# power.net
KiCad netlist of a schematic drawn in Altium Designer
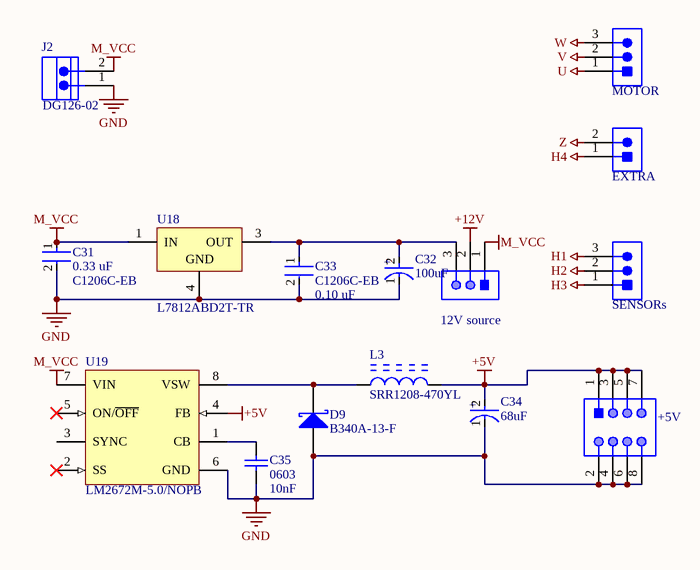
[diagram p0: power.SchDoc]

(export (version "E")
  (design (tool "Eeschema 10.0.6"))
  (components
    (comp (ref "+5V")
      (value "61300821121")
      (footprint "61300821121")
      (description "THT Vertical Pin Header WR-PHD, Pitch 2.54 mm, Dual Row, 8 pins")
      (fields (field (name "MANUFACTURER") "Wurth Elektronik") (field (name "PUBLISHER") "WurthElektronik"))
      (libsource (lib "Altium Content Vault") (part "WE-CN-2P-M-R8"))
    )
    (comp (ref "12V source")
      (value "61300311121")
      (footprint "61300311121")
      (description "THT Vertical Pin Header WR-PHD, Pitch 2.54 mm, Single Row, 3 pins")
      (fields (field (name "MANUFACTURER") "Wurth Elektronik") (field (name "PUBLISHER") "WurthElektronik"))
      (libsource (lib "Altium Content Vault") (part "WE-CN-1P-M-R3"))
    )
    (comp (ref "C31")
      (value "C1206C334M3VACTU")
      (footprint "FP-C1206C-EB-IPC_A")
      (description "CAP CER 0.33UF 25V Y5V 1206")
      (fields
        (field (name "CAPACITANCE") "0.33 uF")
        (field (name "PACKAGE") "C1206C-EB")
        (field (name "OCTOPART") "https://octopart.com/c1206c334m3vactu-kemet-9139506")
        (field (name "TOLERANCE") "0.2")
      )
      (libsource (lib "Altium Content Vault") (part "b4654b650e69147ec39a6b967a45e02"))
    )
    (comp (ref "C32")
      (value "PCR1J101MCL1GS")
      (footprint "FP-PCR1J101MCL1GS-MFG")
      (description "CAP ALUM POLY 100UF 20% 63V SMD")
      (fields
        (field (name "CAPACITANCE") "100uF")
        (field (name "MANUFACTURER") "Nichicon")
        (field (name "TOLERANCE") "20%")
      )
      (libsource (lib "Altium Content Vault") (part "cf48714ba7e38822c1575c7ec0b6d1f"))
    )
    (comp (ref "C33")
      (value "C1206C104KARACTU")
      (footprint "FP-C1206C-EB-IPC_A")
      (description "CAP CER 0.1UF 250V X7R 1206")
      (fields
        (field (name "PACKAGE") "C1206C-EB")
        (field (name "MANUFACTURER") "KEMET")
        (field (name "TOLERANCE") "0.1")
        (field (name "CAPACITANCE") "0.10 uF")
      )
      (libsource (lib "Altium Content Vault") (part "b4654b650e69147ec39a6b967a45e02"))
    )
    (comp (ref "C34")
      (value "PCR1J101MCL1GS")
      (footprint "FP-PCR1J101MCL1GS-MFG")
      (description "CAP ALUM POLY 100UF 20% 63V SMD")
      (fields
        (field (name "CAPACITANCE") "68uF")
        (field (name "MANUFACTURER") "Nichicon")
        (field (name "TOLERANCE") "20%")
      )
      (libsource (lib "Altium Content Vault") (part "cf48714ba7e38822c1575c7ec0b6d1f"))
    )
    (comp (ref "C35")
      (value "10nF")
      (footprint "CAPC0603(1608)100_M")
      (description "CAP 1nF 16V ±2% 0603 (1608 Metric) Thickness 1mm SMD")
      (fields
        (field (name "CASE-EIA") "0603")
        (field (name "TOLERANCE") "Â±2%")
        (field (name "Comment") "CAP 1nF 16V 0603(1608)")
      )
      (libsource (lib "Altium Content Vault") (part "CAP"))
    )
    (comp (ref "D9")
      (value "B340A-13-F")
      (footprint "DIOD-SMA-2_V")
      (libsource (lib "Altium Content Vault") (part "DSKY-AK-2"))
    )
    (comp (ref "EXTRA")
      (value "SCREW-5.0/5.08 2WAYS")
      (footprint "SCREW-5.0-2WAYS_V")
      (description "Socket, Screw Terminal Block, 2 Way, 5.0 mm Pitch, 90 Degree Angle, Through-Hole")
      (fields (field (name "MANUFACTURER") "No Vendor"))
      (libsource (lib "Altium Content Vault") (part "SCREW-2WAYS"))
    )
    (comp (ref "J2")
      (value "DG126-02")
      (footprint "CXKF-KF129C-2_V")
      (fields
        (field (name "PARTNUMBER") "KF129C-02P-14")
        (field (name "MANUFACTURER") "Cixi KaiFeng")
        (field (name "CONTACT") "Brass")
      )
      (libsource (lib "Altium Content Vault") (part "CXKF-KF129C-2"))
    )
    (comp (ref "L3")
      (value "SRR1208-470YL")
      (footprint "BOUR-SRR1280-2_V")
      (fields (field (name "TOLERANCE") "±20%") (field (name "MANUFACTURER") "Bourns"))
      (libsource (lib "Altium Content Vault") (part "IND-FERR-2"))
    )
    (comp (ref "MOTOR")
      (value "SCREW-5.0/5.08 3WAYS")
      (footprint "SCREW-5.0-3WAYS_V")
      (description "Socket, Screw Terminal Block, 3 Way, 5.0 mm Pitch, 90 Degree Angle, Through-Hole")
      (fields (field (name "MANUFACTURER") "No Vendor"))
      (libsource (lib "Altium Content Vault") (part "SCREW-3WAYS"))
    )
    (comp (ref "SENSORs")
      (value "SCREW-5.0/5.08 3WAYS")
      (footprint "SCREW-5.0-3WAYS_V")
      (description "Socket, Screw Terminal Block, 3 Way, 5.0 mm Pitch, 90 Degree Angle, Through-Hole")
      (fields (field (name "MANUFACTURER") "No Vendor"))
      (libsource (lib "Altium Content Vault") (part "SCREW-3WAYS"))
    )
    (comp (ref "U18")
      (value "L7812ABD2T-TR")
      (footprint "TO-263_L")
      (description "Positive Voltage Regulator, 3-Pin D2PAK, Tape and Reel")
      (libsource (lib "Altium Content Vault") (part "PM-REG-L4940-SOT3"))
    )
    (comp (ref "U19")
      (value "LM2672M-5.0/NOPB")
      (footprint "M08A_N")
      (fields (field (name "MANUFACTURER") "National Semiconductor"))
      (libsource (lib "Altium Content Vault") (part "PM-REG-LM2672M-12"))
    )
  )
  (nets
    (net (code "1") (name "+5V") (class "Default")
      (node (ref "+5V") (pin "1") (pinfunction "1_1") (pintype "passive"))
      (node (ref "+5V") (pin "3") (pinfunction "3_3") (pintype "passive"))
      (node (ref "+5V") (pin "5") (pinfunction "5_5") (pintype "passive"))
      (node (ref "+5V") (pin "7") (pinfunction "7_7") (pintype "passive"))
      (node (ref "C34") (pin "2") (pinfunction "A_2") (pintype "passive"))
      (node (ref "L3") (pin "2") (pinfunction "2_2") (pintype "passive"))
      (node (ref "U19") (pin "4") (pinfunction "FB_4") (pintype "input"))
    )
    (net (code "2") (name "+12V") (class "Default")
      (node (ref "12V source") (pin "2") (pinfunction "2_2") (pintype "passive"))
    )
    (net (code "3") (name "GND") (class "Default")
      (node (ref "+5V") (pin "2") (pinfunction "2_2") (pintype "passive"))
      (node (ref "+5V") (pin "4") (pinfunction "4_4") (pintype "passive"))
      (node (ref "+5V") (pin "6") (pinfunction "6_6") (pintype "passive"))
      (node (ref "+5V") (pin "8") (pinfunction "8_8") (pintype "passive"))
      (node (ref "C31") (pin "2") (pinfunction "2_2") (pintype "passive"))
      (node (ref "C32") (pin "1") (pinfunction "C_1") (pintype "passive"))
      (node (ref "C33") (pin "2") (pinfunction "2_2") (pintype "passive"))
      (node (ref "C34") (pin "1") (pinfunction "C_1") (pintype "passive"))
      (node (ref "C35") (pin "1") (pinfunction "1_1") (pintype "passive"))
      (node (ref "D9") (pin "1") (pinfunction "A_1") (pintype "passive"))
      (node (ref "J2") (pin "1") (pinfunction "1_1") (pintype "passive"))
      (node (ref "U18") (pin "4") (pinfunction "GND_4") (pintype "power_in"))
      (node (ref "U19") (pin "6") (pinfunction "GND_6") (pintype "power_in"))
    )
    (net (code "4") (name "H1") (class "Default")
      (node (ref "SENSORs") (pin "3") (pinfunction "3_3") (pintype "passive"))
    )
    (net (code "5") (name "H2") (class "Default")
      (node (ref "SENSORs") (pin "2") (pinfunction "2_2") (pintype "passive"))
    )
    (net (code "6") (name "H3") (class "Default")
      (node (ref "SENSORs") (pin "1") (pinfunction "1_1") (pintype "passive"))
    )
    (net (code "7") (name "H4") (class "Default")
      (node (ref "EXTRA") (pin "1") (pinfunction "1_1") (pintype "passive"))
    )
    (net (code "8") (name "M_VCC") (class "Default")
      (node (ref "12V source") (pin "1") (pinfunction "1_1") (pintype "passive"))
      (node (ref "C31") (pin "1") (pinfunction "1_1") (pintype "passive"))
      (node (ref "J2") (pin "2") (pinfunction "2_2") (pintype "passive"))
      (node (ref "U18") (pin "1") (pinfunction "IN_1") (pintype "power_in"))
      (node (ref "U19") (pin "7") (pinfunction "VIN_7") (pintype "power_in"))
    )
    (net (code "9") (name "Net-(C32-A)") (class "Default")
      (node (ref "12V source") (pin "3") (pinfunction "3_3") (pintype "passive"))
      (node (ref "C32") (pin "2") (pinfunction "A_2") (pintype "passive"))
      (node (ref "C33") (pin "1") (pinfunction "1_1") (pintype "passive"))
      (node (ref "U18") (pin "3") (pinfunction "OUT_3") (pintype "power_in"))
    )
    (net (code "10") (name "Net-(D9-K)") (class "Default")
      (node (ref "D9") (pin "2") (pinfunction "K_2") (pintype "passive"))
      (node (ref "L3") (pin "1") (pinfunction "1_1") (pintype "passive"))
      (node (ref "U19") (pin "8") (pinfunction "VSW_8") (pintype "power_in"))
    )
    (net (code "11") (name "Net-(U19-CB)") (class "Default")
      (node (ref "C35") (pin "2") (pinfunction "2_2") (pintype "passive"))
      (node (ref "U19") (pin "1") (pinfunction "CB_1") (pintype "passive"))
    )
    (net (code "12") (name "U") (class "Default")
      (node (ref "MOTOR") (pin "1") (pinfunction "1_1") (pintype "passive"))
    )
    (net (code "13") (name "V") (class "Default")
      (node (ref "MOTOR") (pin "2") (pinfunction "2_2") (pintype "passive"))
    )
    (net (code "14") (name "W") (class "Default")
      (node (ref "MOTOR") (pin "3") (pinfunction "3_3") (pintype "passive"))
    )
    (net (code "15") (name "Z") (class "Default")
      (node (ref "EXTRA") (pin "2") (pinfunction "2_2") (pintype "passive"))
    )
    (net (code "16") (name "unconnected-(U19-ON{slash}~{OFF}-Pad5)") (class "Default")
      (node (ref "U19") (pin "5") (pinfunction "ON/~{OFF}_5") (pintype "input+no_connect"))
    )
    (net (code "17") (name "unconnected-(U19-SS-Pad2)") (class "Default")
      (node (ref "U19") (pin "2") (pinfunction "SS_2") (pintype "input+no_connect"))
    )
    (net (code "18") (name "unconnected-(U19-SYNC-Pad3)") (class "Default")
      (node (ref "U19") (pin "3") (pinfunction "SYNC_3") (pintype "passive"))
    )
  )
)
